# FPGA_DECOUP.net
KiCad netlist of a schematic drawn in Altium Designer
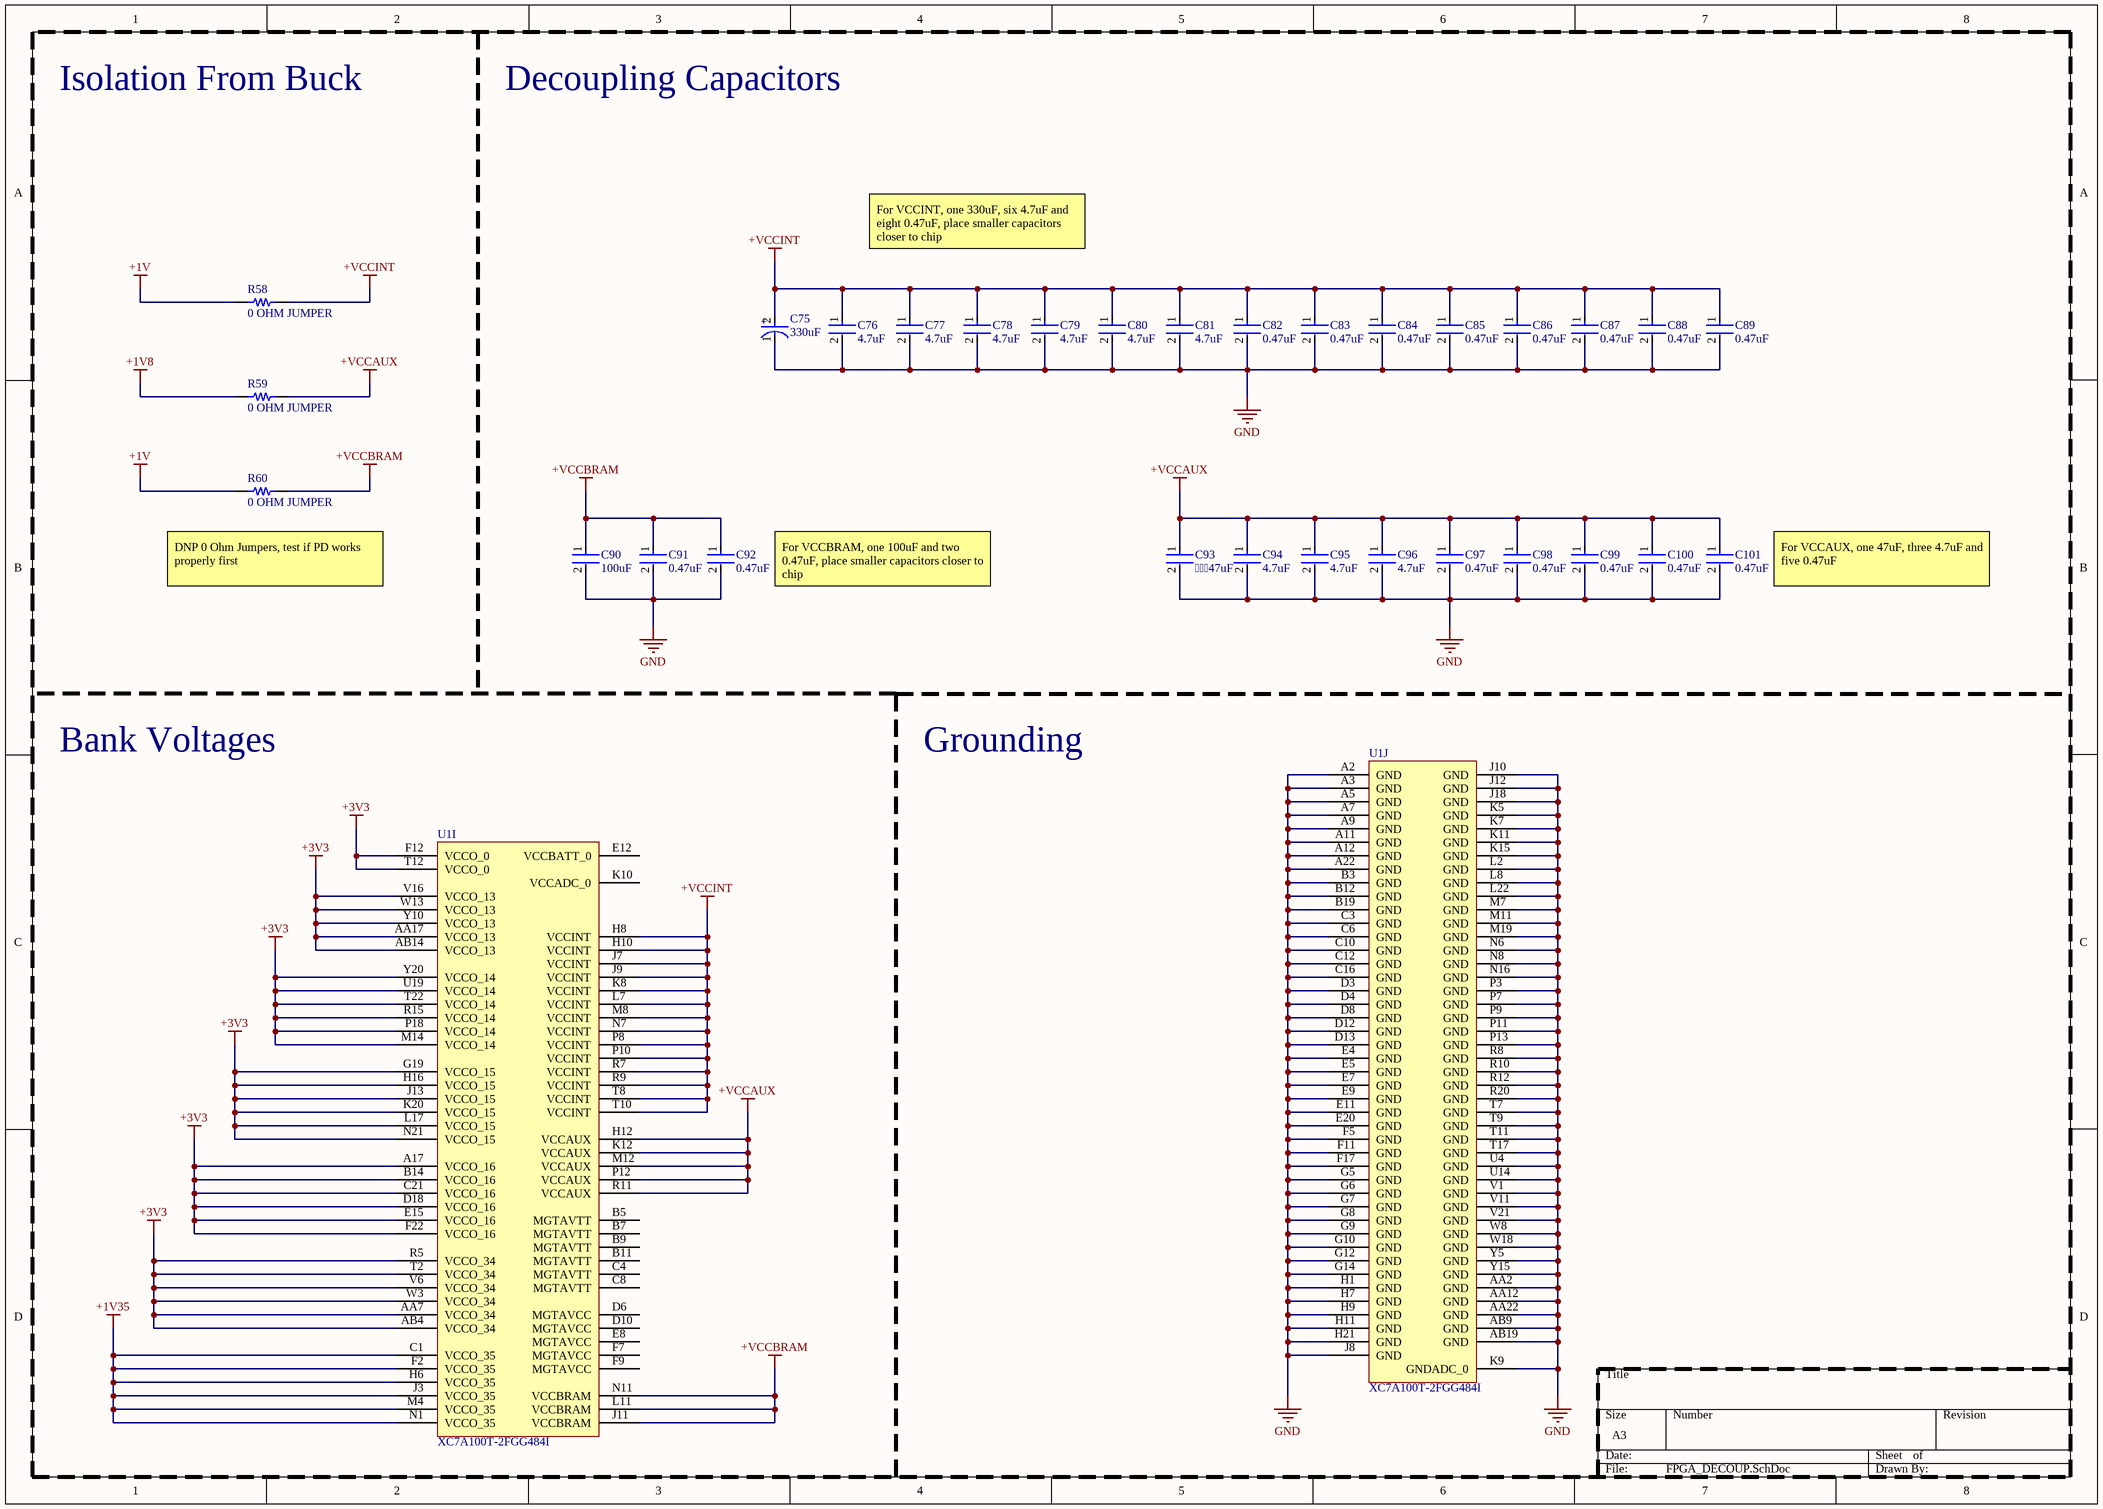
[diagram p0: FPGA_DECOUP.SchDoc]

(export (version "E")
  (design (tool "Eeschema 10.0.6"))
  (components
    (comp (ref "C75")
      (value "330uF")
      (footprint "FP-T495X336M035ATE100-MFG")
      (description "CAP TANT 33UF 20% 35V 2917")
      (fields (field (name "TOLERANCE") "20%"))
      (libsource (lib "Altium Content Vault") (part "203bc49f2ac43e59fd269a8c329ed05"))
    )
    (comp (ref "C76")
      (value "4.7uF")
      (footprint "FP-GRM155-0_1-IPC_B")
      (description "Chip Multilayer Ceramic Capacitors for General Purpose, 0402, 4.7uF, X5R, 15%, 20%, 6.3V")
      (fields (field (name "VOLTAGE") "6.3V") (field (name "TOLERANCE") "20%"))
      (libsource (lib "Altium Content Vault") (part "11868f565c42a9108669ba33697ecf6"))
    )
    (comp (ref "C77")
      (value "4.7uF")
      (footprint "FP-GRM155-0_1-IPC_B")
      (description "Chip Multilayer Ceramic Capacitors for General Purpose, 0402, 4.7uF, X5R, 15%, 20%, 6.3V")
      (fields (field (name "VOLTAGE") "6.3V") (field (name "TOLERANCE") "20%"))
      (libsource (lib "Altium Content Vault") (part "11868f565c42a9108669ba33697ecf6"))
    )
    (comp (ref "C78")
      (value "4.7uF")
      (footprint "FP-GRM155-0_1-IPC_B")
      (description "Chip Multilayer Ceramic Capacitors for General Purpose, 0402, 4.7uF, X5R, 15%, 20%, 6.3V")
      (fields (field (name "VOLTAGE") "6.3V") (field (name "TOLERANCE") "20%"))
      (libsource (lib "Altium Content Vault") (part "11868f565c42a9108669ba33697ecf6"))
    )
    (comp (ref "C79")
      (value "4.7uF")
      (footprint "FP-GRM155-0_1-IPC_B")
      (description "Chip Multilayer Ceramic Capacitors for General Purpose, 0402, 4.7uF, X5R, 15%, 20%, 6.3V")
      (fields (field (name "VOLTAGE") "6.3V") (field (name "TOLERANCE") "20%"))
      (libsource (lib "Altium Content Vault") (part "11868f565c42a9108669ba33697ecf6"))
    )
    (comp (ref "C80")
      (value "4.7uF")
      (footprint "FP-GRM155-0_1-IPC_B")
      (description "Chip Multilayer Ceramic Capacitors for General Purpose, 0402, 4.7uF, X5R, 15%, 20%, 6.3V")
      (fields (field (name "VOLTAGE") "6.3V") (field (name "TOLERANCE") "20%"))
      (libsource (lib "Altium Content Vault") (part "11868f565c42a9108669ba33697ecf6"))
    )
    (comp (ref "C81")
      (value "4.7uF")
      (footprint "FP-GRM155-0_1-IPC_B")
      (description "Chip Multilayer Ceramic Capacitors for General Purpose, 0402, 4.7uF, X5R, 15%, 20%, 6.3V")
      (fields (field (name "VOLTAGE") "6.3V") (field (name "TOLERANCE") "20%"))
      (libsource (lib "Altium Content Vault") (part "11868f565c42a9108669ba33697ecf6"))
    )
    (comp (ref "C82")
      (value "0.47uF")
      (footprint "FP-GRM15-0_1-MFG")
      (description "CAP CER 0.47UF 10V X5R 0402")
      (fields
        (field (name "MANUFACTURER") "Murata Electronics North America")
        (field (name "MANUFACTURER PART NUMBER") "GRM155R61A474KE15D")
      )
      (libsource (lib "Altium Content Vault") (part "11868f565c42a9108669ba33697ecf6"))
    )
    (comp (ref "C83")
      (value "0.47uF")
      (footprint "FP-GRM15-0_1-MFG")
      (description "CAP CER 0.47UF 10V X5R 0402")
      (fields
        (field (name "MANUFACTURER") "Murata Electronics North America")
        (field (name "MANUFACTURER PART NUMBER") "GRM155R61A474KE15D")
      )
      (libsource (lib "Altium Content Vault") (part "11868f565c42a9108669ba33697ecf6"))
    )
    (comp (ref "C84")
      (value "0.47uF")
      (footprint "FP-GRM15-0_1-MFG")
      (description "CAP CER 0.47UF 10V X5R 0402")
      (fields
        (field (name "MANUFACTURER") "Murata Electronics North America")
        (field (name "MANUFACTURER PART NUMBER") "GRM155R61A474KE15D")
      )
      (libsource (lib "Altium Content Vault") (part "11868f565c42a9108669ba33697ecf6"))
    )
    (comp (ref "C85")
      (value "0.47uF")
      (footprint "FP-GRM15-0_1-MFG")
      (description "CAP CER 0.47UF 10V X5R 0402")
      (fields
        (field (name "MANUFACTURER") "Murata Electronics North America")
        (field (name "MANUFACTURER PART NUMBER") "GRM155R61A474KE15D")
      )
      (libsource (lib "Altium Content Vault") (part "11868f565c42a9108669ba33697ecf6"))
    )
    (comp (ref "C86")
      (value "0.47uF")
      (footprint "FP-GRM15-0_1-MFG")
      (description "CAP CER 0.47UF 10V X5R 0402")
      (fields
        (field (name "MANUFACTURER") "Murata Electronics North America")
        (field (name "MANUFACTURER PART NUMBER") "GRM155R61A474KE15D")
      )
      (libsource (lib "Altium Content Vault") (part "11868f565c42a9108669ba33697ecf6"))
    )
    (comp (ref "C87")
      (value "0.47uF")
      (footprint "FP-GRM15-0_1-MFG")
      (description "CAP CER 0.47UF 10V X5R 0402")
      (fields
        (field (name "MANUFACTURER") "Murata Electronics North America")
        (field (name "MANUFACTURER PART NUMBER") "GRM155R61A474KE15D")
      )
      (libsource (lib "Altium Content Vault") (part "11868f565c42a9108669ba33697ecf6"))
    )
    (comp (ref "C88")
      (value "0.47uF")
      (footprint "FP-GRM15-0_1-MFG")
      (description "CAP CER 0.47UF 10V X5R 0402")
      (fields
        (field (name "MANUFACTURER") "Murata Electronics North America")
        (field (name "MANUFACTURER PART NUMBER") "GRM155R61A474KE15D")
      )
      (libsource (lib "Altium Content Vault") (part "11868f565c42a9108669ba33697ecf6"))
    )
    (comp (ref "C89")
      (value "0.47uF")
      (footprint "FP-GRM15-0_1-MFG")
      (description "CAP CER 0.47UF 10V X5R 0402")
      (fields
        (field (name "MANUFACTURER") "Murata Electronics North America")
        (field (name "MANUFACTURER PART NUMBER") "GRM155R61A474KE15D")
      )
      (libsource (lib "Altium Content Vault") (part "11868f565c42a9108669ba33697ecf6"))
    )
    (comp (ref "C90")
      (value "100uF")
      (footprint "FP-GRM32E-0_3-0_2-IPC_B")
      (description "Chip Multilayer Ceramic Capacitors for General Purpose, 1210, 100uF, X5R, 15%, 20%, 10V")
      (fields (field (name "TOLERANCE") "20%") (field (name "VOLTAGE") "10V"))
      (libsource (lib "Altium Content Vault") (part "02cd4be3c70576c341d710602a673aa"))
    )
    (comp (ref "C91")
      (value "0.47uF")
      (footprint "FP-GRM15-0_1-MFG")
      (description "CAP CER 0.47UF 10V X5R 0402")
      (fields
        (field (name "MANUFACTURER") "Murata Electronics North America")
        (field (name "MANUFACTURER PART NUMBER") "GRM155R61A474KE15D")
      )
      (libsource (lib "Altium Content Vault") (part "11868f565c42a9108669ba33697ecf6"))
    )
    (comp (ref "C92")
      (value "0.47uF")
      (footprint "FP-GRM15-0_1-MFG")
      (description "CAP CER 0.47UF 10V X5R 0402")
      (fields
        (field (name "MANUFACTURER") "Murata Electronics North America")
        (field (name "MANUFACTURER PART NUMBER") "GRM155R61A474KE15D")
      )
      (libsource (lib "Altium Content Vault") (part "11868f565c42a9108669ba33697ecf6"))
    )
    (comp (ref "C93")
      (value "47uF")
      (footprint "FP-GRM32E-0_3-0_2-MFG")
      (description "CAP CER 47UF 6.3V X5R 1210")
      (fields (field (name "VOLTAGE") "6.3V") (field (name "TOLERANCE") "10%"))
      (libsource (lib "Altium Content Vault") (part "02cd4be3c70576c341d710602a673aa"))
    )
    (comp (ref "C94")
      (value "4.7uF")
      (footprint "FP-GRM155-0_1-IPC_B")
      (description "Chip Multilayer Ceramic Capacitors for General Purpose, 0402, 4.7uF, X5R, 15%, 20%, 6.3V")
      (fields (field (name "VOLTAGE") "6.3V") (field (name "TOLERANCE") "20%"))
      (libsource (lib "Altium Content Vault") (part "11868f565c42a9108669ba33697ecf6"))
    )
    (comp (ref "C95")
      (value "4.7uF")
      (footprint "FP-GRM155-0_1-IPC_B")
      (description "Chip Multilayer Ceramic Capacitors for General Purpose, 0402, 4.7uF, X5R, 15%, 20%, 6.3V")
      (fields (field (name "VOLTAGE") "6.3V") (field (name "TOLERANCE") "20%"))
      (libsource (lib "Altium Content Vault") (part "11868f565c42a9108669ba33697ecf6"))
    )
    (comp (ref "C96")
      (value "4.7uF")
      (footprint "FP-GRM155-0_1-IPC_B")
      (description "Chip Multilayer Ceramic Capacitors for General Purpose, 0402, 4.7uF, X5R, 15%, 20%, 6.3V")
      (fields (field (name "VOLTAGE") "6.3V") (field (name "TOLERANCE") "20%"))
      (libsource (lib "Altium Content Vault") (part "11868f565c42a9108669ba33697ecf6"))
    )
    (comp (ref "C97")
      (value "0.47uF")
      (footprint "FP-GRM15-0_1-MFG")
      (description "CAP CER 0.47UF 10V X5R 0402")
      (fields
        (field (name "MANUFACTURER") "Murata Electronics North America")
        (field (name "MANUFACTURER PART NUMBER") "GRM155R61A474KE15D")
      )
      (libsource (lib "Altium Content Vault") (part "11868f565c42a9108669ba33697ecf6"))
    )
    (comp (ref "C98")
      (value "0.47uF")
      (footprint "FP-GRM15-0_1-MFG")
      (description "CAP CER 0.47UF 10V X5R 0402")
      (fields
        (field (name "MANUFACTURER") "Murata Electronics North America")
        (field (name "MANUFACTURER PART NUMBER") "GRM155R61A474KE15D")
      )
      (libsource (lib "Altium Content Vault") (part "11868f565c42a9108669ba33697ecf6"))
    )
    (comp (ref "C99")
      (value "0.47uF")
      (footprint "FP-GRM15-0_1-MFG")
      (description "CAP CER 0.47UF 10V X5R 0402")
      (fields
        (field (name "MANUFACTURER") "Murata Electronics North America")
        (field (name "MANUFACTURER PART NUMBER") "GRM155R61A474KE15D")
      )
      (libsource (lib "Altium Content Vault") (part "11868f565c42a9108669ba33697ecf6"))
    )
    (comp (ref "C100")
      (value "0.47uF")
      (footprint "FP-GRM15-0_1-MFG")
      (description "CAP CER 0.47UF 10V X5R 0402")
      (fields
        (field (name "MANUFACTURER") "Murata Electronics North America")
        (field (name "MANUFACTURER PART NUMBER") "GRM155R61A474KE15D")
      )
      (libsource (lib "Altium Content Vault") (part "11868f565c42a9108669ba33697ecf6"))
    )
    (comp (ref "C101")
      (value "0.47uF")
      (footprint "FP-GRM15-0_1-MFG")
      (description "CAP CER 0.47UF 10V X5R 0402")
      (fields
        (field (name "MANUFACTURER") "Murata Electronics North America")
        (field (name "MANUFACTURER PART NUMBER") "GRM155R61A474KE15D")
      )
      (libsource (lib "Altium Content Vault") (part "11868f565c42a9108669ba33697ecf6"))
    )
    (comp (ref "R58")
      (value "0 OHM JUMPER")
      (footprint "RES 0603_1608")
      (description "Fixed Resistor, Metal Glaze/thick Film, 0.1W, 0ohm, Surface Mount, 0603")
      (libsource (lib "Midnight Sun") (part "Resistor"))
    )
    (comp (ref "R59")
      (value "0 OHM JUMPER")
      (footprint "RES 0603_1608")
      (description "Fixed Resistor, Metal Glaze/thick Film, 0.1W, 0ohm, Surface Mount, 0603")
      (libsource (lib "Midnight Sun") (part "Resistor"))
    )
    (comp (ref "R60")
      (value "0 OHM JUMPER")
      (footprint "RES 0603_1608")
      (description "Fixed Resistor, Metal Glaze/thick Film, 0.1W, 0ohm, Surface Mount, 0603")
      (libsource (lib "Midnight Sun") (part "Resistor"))
    )
    (comp (ref "U1")
      (value "XC7A100T-2FGG484I")
      (footprint "FGG484")
      (description "Artix-7 FPGA, 285 User I/Os, 4 GTP, 484-Ball BGA, Speed Grade 2, Industrial Grade, Pb-Free")
      (fields (field (name "MANUFACTURER") "Xilinx") (field (name "GENERIC PART NUMBER") "XC7A100T"))
      (libsource (lib "Altium Content Vault") (part "XNLX-XC7A100T-XNLX-FGG484"))
    )
  )
  (nets
    (net (code "1") (name "+1V") (class "Default")
      (node (ref "R58") (pin "1") (pinfunction "1_1") (pintype "passive"))
      (node (ref "R60") (pin "1") (pinfunction "1_1") (pintype "passive"))
    )
    (net (code "2") (name "+1V8") (class "Default")
      (node (ref "R59") (pin "1") (pinfunction "1_1") (pintype "passive"))
    )
    (net (code "3") (name "+1V35") (class "Default")
      (node (ref "U1") (pin "C1") (pinfunction "VCCO_35_C1") (pintype "power_in"))
      (node (ref "U1") (pin "F2") (pinfunction "VCCO_35_F2") (pintype "power_in"))
      (node (ref "U1") (pin "H6") (pinfunction "VCCO_35_H6") (pintype "power_in"))
      (node (ref "U1") (pin "J3") (pinfunction "VCCO_35_J3") (pintype "power_in"))
      (node (ref "U1") (pin "M4") (pinfunction "VCCO_35_M4") (pintype "power_in"))
      (node (ref "U1") (pin "N1") (pinfunction "VCCO_35_N1") (pintype "power_in"))
    )
    (net (code "4") (name "+3V3") (class "Default")
      (node (ref "U1") (pin "A17") (pinfunction "VCCO_16_A17") (pintype "power_in"))
      (node (ref "U1") (pin "AA17") (pinfunction "VCCO_13_AA17") (pintype "power_in"))
      (node (ref "U1") (pin "AA7") (pinfunction "VCCO_34_AA7") (pintype "power_in"))
      (node (ref "U1") (pin "AB14") (pinfunction "VCCO_13_AB14") (pintype "power_in"))
      (node (ref "U1") (pin "AB4") (pinfunction "VCCO_34_AB4") (pintype "power_in"))
      (node (ref "U1") (pin "B14") (pinfunction "VCCO_16_B14") (pintype "power_in"))
      (node (ref "U1") (pin "C21") (pinfunction "VCCO_16_C21") (pintype "power_in"))
      (node (ref "U1") (pin "D18") (pinfunction "VCCO_16_D18") (pintype "power_in"))
      (node (ref "U1") (pin "E15") (pinfunction "VCCO_16_E15") (pintype "power_in"))
      (node (ref "U1") (pin "F12") (pinfunction "VCCO_0_F12") (pintype "power_in"))
      (node (ref "U1") (pin "F22") (pinfunction "VCCO_16_F22") (pintype "power_in"))
      (node (ref "U1") (pin "G19") (pinfunction "VCCO_15_G19") (pintype "power_in"))
      (node (ref "U1") (pin "H16") (pinfunction "VCCO_15_H16") (pintype "power_in"))
      (node (ref "U1") (pin "J13") (pinfunction "VCCO_15_J13") (pintype "power_in"))
      (node (ref "U1") (pin "K20") (pinfunction "VCCO_15_K20") (pintype "power_in"))
      (node (ref "U1") (pin "L17") (pinfunction "VCCO_15_L17") (pintype "power_in"))
      (node (ref "U1") (pin "M14") (pinfunction "VCCO_14_M14") (pintype "power_in"))
      (node (ref "U1") (pin "N21") (pinfunction "VCCO_15_N21") (pintype "power_in"))
      (node (ref "U1") (pin "P18") (pinfunction "VCCO_14_P18") (pintype "power_in"))
      (node (ref "U1") (pin "R15") (pinfunction "VCCO_14_R15") (pintype "power_in"))
      (node (ref "U1") (pin "R5") (pinfunction "VCCO_34_R5") (pintype "power_in"))
      (node (ref "U1") (pin "T12") (pinfunction "VCCO_0_T12") (pintype "power_in"))
      (node (ref "U1") (pin "T2") (pinfunction "VCCO_34_T2") (pintype "power_in"))
      (node (ref "U1") (pin "T22") (pinfunction "VCCO_14_T22") (pintype "power_in"))
      (node (ref "U1") (pin "U19") (pinfunction "VCCO_14_U19") (pintype "power_in"))
      (node (ref "U1") (pin "V16") (pinfunction "VCCO_13_V16") (pintype "power_in"))
      (node (ref "U1") (pin "V6") (pinfunction "VCCO_34_V6") (pintype "power_in"))
      (node (ref "U1") (pin "W13") (pinfunction "VCCO_13_W13") (pintype "power_in"))
      (node (ref "U1") (pin "W3") (pinfunction "VCCO_34_W3") (pintype "power_in"))
      (node (ref "U1") (pin "Y10") (pinfunction "VCCO_13_Y10") (pintype "power_in"))
      (node (ref "U1") (pin "Y20") (pinfunction "VCCO_14_Y20") (pintype "power_in"))
    )
    (net (code "5") (name "+VCCAUX") (class "Default")
      (node (ref "C100") (pin "1") (pinfunction "1_1") (pintype "passive"))
      (node (ref "C101") (pin "1") (pinfunction "1_1") (pintype "passive"))
      (node (ref "C93") (pin "1") (pinfunction "1_1") (pintype "passive"))
      (node (ref "C94") (pin "1") (pinfunction "1_1") (pintype "passive"))
      (node (ref "C95") (pin "1") (pinfunction "1_1") (pintype "passive"))
      (node (ref "C96") (pin "1") (pinfunction "1_1") (pintype "passive"))
      (node (ref "C97") (pin "1") (pinfunction "1_1") (pintype "passive"))
      (node (ref "C98") (pin "1") (pinfunction "1_1") (pintype "passive"))
      (node (ref "C99") (pin "1") (pinfunction "1_1") (pintype "passive"))
      (node (ref "R59") (pin "2") (pinfunction "2_2") (pintype "passive"))
      (node (ref "U1") (pin "H12") (pinfunction "VCCAUX_H12") (pintype "power_in"))
      (node (ref "U1") (pin "K12") (pinfunction "VCCAUX_K12") (pintype "power_in"))
      (node (ref "U1") (pin "M12") (pinfunction "VCCAUX_M12") (pintype "power_in"))
      (node (ref "U1") (pin "P12") (pinfunction "VCCAUX_P12") (pintype "power_in"))
      (node (ref "U1") (pin "R11") (pinfunction "VCCAUX_R11") (pintype "power_in"))
    )
    (net (code "6") (name "+VCCBRAM") (class "Default")
      (node (ref "C90") (pin "1") (pinfunction "1_1") (pintype "passive"))
      (node (ref "C91") (pin "1") (pinfunction "1_1") (pintype "passive"))
      (node (ref "C92") (pin "1") (pinfunction "1_1") (pintype "passive"))
      (node (ref "R60") (pin "2") (pinfunction "2_2") (pintype "passive"))
      (node (ref "U1") (pin "J11") (pinfunction "VCCBRAM_J11") (pintype "power_in"))
      (node (ref "U1") (pin "L11") (pinfunction "VCCBRAM_L11") (pintype "power_in"))
      (node (ref "U1") (pin "N11") (pinfunction "VCCBRAM_N11") (pintype "power_in"))
    )
    (net (code "7") (name "+VCCINT") (class "Default")
      (node (ref "C75") (pin "2") (pinfunction "A_2") (pintype "passive"))
      (node (ref "C76") (pin "1") (pinfunction "1_1") (pintype "passive"))
      (node (ref "C77") (pin "1") (pinfunction "1_1") (pintype "passive"))
      (node (ref "C78") (pin "1") (pinfunction "1_1") (pintype "passive"))
      (node (ref "C79") (pin "1") (pinfunction "1_1") (pintype "passive"))
      (node (ref "C80") (pin "1") (pinfunction "1_1") (pintype "passive"))
      (node (ref "C81") (pin "1") (pinfunction "1_1") (pintype "passive"))
      (node (ref "C82") (pin "1") (pinfunction "1_1") (pintype "passive"))
      (node (ref "C83") (pin "1") (pinfunction "1_1") (pintype "passive"))
      (node (ref "C84") (pin "1") (pinfunction "1_1") (pintype "passive"))
      (node (ref "C85") (pin "1") (pinfunction "1_1") (pintype "passive"))
      (node (ref "C86") (pin "1") (pinfunction "1_1") (pintype "passive"))
      (node (ref "C87") (pin "1") (pinfunction "1_1") (pintype "passive"))
      (node (ref "C88") (pin "1") (pinfunction "1_1") (pintype "passive"))
      (node (ref "C89") (pin "1") (pinfunction "1_1") (pintype "passive"))
      (node (ref "R58") (pin "2") (pinfunction "2_2") (pintype "passive"))
      (node (ref "U1") (pin "H10") (pinfunction "VCCINT_H10") (pintype "power_in"))
      (node (ref "U1") (pin "H8") (pinfunction "VCCINT_H8") (pintype "power_in"))
      (node (ref "U1") (pin "J7") (pinfunction "VCCINT_J7") (pintype "power_in"))
      (node (ref "U1") (pin "J9") (pinfunction "VCCINT_J9") (pintype "power_in"))
      (node (ref "U1") (pin "K8") (pinfunction "VCCINT_K8") (pintype "power_in"))
      (node (ref "U1") (pin "L7") (pinfunction "VCCINT_L7") (pintype "power_in"))
      (node (ref "U1") (pin "M8") (pinfunction "VCCINT_M8") (pintype "power_in"))
      (node (ref "U1") (pin "N7") (pinfunction "VCCINT_N7") (pintype "power_in"))
      (node (ref "U1") (pin "P10") (pinfunction "VCCINT_P10") (pintype "power_in"))
      (node (ref "U1") (pin "P8") (pinfunction "VCCINT_P8") (pintype "power_in"))
      (node (ref "U1") (pin "R7") (pinfunction "VCCINT_R7") (pintype "power_in"))
      (node (ref "U1") (pin "R9") (pinfunction "VCCINT_R9") (pintype "power_in"))
      (node (ref "U1") (pin "T10") (pinfunction "VCCINT_T10") (pintype "power_in"))
      (node (ref "U1") (pin "T8") (pinfunction "VCCINT_T8") (pintype "power_in"))
    )
    (net (code "8") (name "GND") (class "Default")
      (node (ref "C100") (pin "2") (pinfunction "2_2") (pintype "passive"))
      (node (ref "C101") (pin "2") (pinfunction "2_2") (pintype "passive"))
      (node (ref "C75") (pin "1") (pinfunction "C_1") (pintype "passive"))
      (node (ref "C76") (pin "2") (pinfunction "2_2") (pintype "passive"))
      (node (ref "C77") (pin "2") (pinfunction "2_2") (pintype "passive"))
      (node (ref "C78") (pin "2") (pinfunction "2_2") (pintype "passive"))
      (node (ref "C79") (pin "2") (pinfunction "2_2") (pintype "passive"))
      (node (ref "C80") (pin "2") (pinfunction "2_2") (pintype "passive"))
      (node (ref "C81") (pin "2") (pinfunction "2_2") (pintype "passive"))
      (node (ref "C82") (pin "2") (pinfunction "2_2") (pintype "passive"))
      (node (ref "C83") (pin "2") (pinfunction "2_2") (pintype "passive"))
      (node (ref "C84") (pin "2") (pinfunction "2_2") (pintype "passive"))
      (node (ref "C85") (pin "2") (pinfunction "2_2") (pintype "passive"))
      (node (ref "C86") (pin "2") (pinfunction "2_2") (pintype "passive"))
      (node (ref "C87") (pin "2") (pinfunction "2_2") (pintype "passive"))
      (node (ref "C88") (pin "2") (pinfunction "2_2") (pintype "passive"))
      (node (ref "C89") (pin "2") (pinfunction "2_2") (pintype "passive"))
      (node (ref "C90") (pin "2") (pinfunction "2_2") (pintype "passive"))
      (node (ref "C91") (pin "2") (pinfunction "2_2") (pintype "passive"))
      (node (ref "C92") (pin "2") (pinfunction "2_2") (pintype "passive"))
      (node (ref "C93") (pin "2") (pinfunction "2_2") (pintype "passive"))
      (node (ref "C94") (pin "2") (pinfunction "2_2") (pintype "passive"))
      (node (ref "C95") (pin "2") (pinfunction "2_2") (pintype "passive"))
      (node (ref "C96") (pin "2") (pinfunction "2_2") (pintype "passive"))
      (node (ref "C97") (pin "2") (pinfunction "2_2") (pintype "passive"))
      (node (ref "C98") (pin "2") (pinfunction "2_2") (pintype "passive"))
      (node (ref "C99") (pin "2") (pinfunction "2_2") (pintype "passive"))
      (node (ref "U1") (pin "A11") (pinfunction "GND_A11") (pintype "power_in"))
      (node (ref "U1") (pin "A12") (pinfunction "GND_A12") (pintype "power_in"))
      (node (ref "U1") (pin "A2") (pinfunction "GND_A2") (pintype "power_in"))
      (node (ref "U1") (pin "A22") (pinfunction "GND_A22") (pintype "power_in"))
      (node (ref "U1") (pin "A3") (pinfunction "GND_A3") (pintype "power_in"))
      (node (ref "U1") (pin "A5") (pinfunction "GND_A5") (pintype "power_in"))
      (node (ref "U1") (pin "A7") (pinfunction "GND_A7") (pintype "power_in"))
      (node (ref "U1") (pin "A9") (pinfunction "GND_A9") (pintype "power_in"))
      (node (ref "U1") (pin "AA12") (pinfunction "GND_AA12") (pintype "power_in"))
      (node (ref "U1") (pin "AA2") (pinfunction "GND_AA2") (pintype "power_in"))
      (node (ref "U1") (pin "AA22") (pinfunction "GND_AA22") (pintype "power_in"))
      (node (ref "U1") (pin "AB19") (pinfunction "GND_AB19") (pintype "power_in"))
      (node (ref "U1") (pin "AB9") (pinfunction "GND_AB9") (pintype "power_in"))
      (node (ref "U1") (pin "B12") (pinfunction "GND_B12") (pintype "power_in"))
      (node (ref "U1") (pin "B19") (pinfunction "GND_B19") (pintype "power_in"))
      (node (ref "U1") (pin "B3") (pinfunction "GND_B3") (pintype "power_in"))
      (node (ref "U1") (pin "C10") (pinfunction "GND_C10") (pintype "power_in"))
      (node (ref "U1") (pin "C12") (pinfunction "GND_C12") (pintype "power_in"))
      (node (ref "U1") (pin "C16") (pinfunction "GND_C16") (pintype "power_in"))
      (node (ref "U1") (pin "C3") (pinfunction "GND_C3") (pintype "power_in"))
      (node (ref "U1") (pin "C6") (pinfunction "GND_C6") (pintype "power_in"))
      (node (ref "U1") (pin "D12") (pinfunction "GND_D12") (pintype "power_in"))
      (node (ref "U1") (pin "D13") (pinfunction "GND_D13") (pintype "power_in"))
      (node (ref "U1") (pin "D3") (pinfunction "GND_D3") (pintype "power_in"))
      (node (ref "U1") (pin "D4") (pinfunction "GND_D4") (pintype "power_in"))
      (node (ref "U1") (pin "D8") (pinfunction "GND_D8") (pintype "power_in"))
      (node (ref "U1") (pin "E11") (pinfunction "GND_E11") (pintype "power_in"))
      (node (ref "U1") (pin "E20") (pinfunction "GND_E20") (pintype "power_in"))
      (node (ref "U1") (pin "E4") (pinfunction "GND_E4") (pintype "power_in"))
      (node (ref "U1") (pin "E5") (pinfunction "GND_E5") (pintype "power_in"))
      (node (ref "U1") (pin "E7") (pinfunction "GND_E7") (pintype "power_in"))
      (node (ref "U1") (pin "E9") (pinfunction "GND_E9") (pintype "power_in"))
      (node (ref "U1") (pin "F11") (pinfunction "GND_F11") (pintype "power_in"))
      (node (ref "U1") (pin "F17") (pinfunction "GND_F17") (pintype "power_in"))
      (node (ref "U1") (pin "F5") (pinfunction "GND_F5") (pintype "power_in"))
      (node (ref "U1") (pin "G10") (pinfunction "GND_G10") (pintype "power_in"))
      (node (ref "U1") (pin "G12") (pinfunction "GND_G12") (pintype "power_in"))
      (node (ref "U1") (pin "G14") (pinfunction "GND_G14") (pintype "power_in"))
      (node (ref "U1") (pin "G5") (pinfunction "GND_G5") (pintype "power_in"))
      (node (ref "U1") (pin "G6") (pinfunction "GND_G6") (pintype "power_in"))
      (node (ref "U1") (pin "G7") (pinfunction "GND_G7") (pintype "power_in"))
      (node (ref "U1") (pin "G8") (pinfunction "GND_G8") (pintype "power_in"))
      (node (ref "U1") (pin "G9") (pinfunction "GND_G9") (pintype "power_in"))
      (node (ref "U1") (pin "H1") (pinfunction "GND_H1") (pintype "power_in"))
      (node (ref "U1") (pin "H11") (pinfunction "GND_H11") (pintype "power_in"))
      (node (ref "U1") (pin "H21") (pinfunction "GND_H21") (pintype "power_in"))
      (node (ref "U1") (pin "H7") (pinfunction "GND_H7") (pintype "power_in"))
      (node (ref "U1") (pin "H9") (pinfunction "GND_H9") (pintype "power_in"))
      (node (ref "U1") (pin "J10") (pinfunction "GND_J10") (pintype "power_in"))
      (node (ref "U1") (pin "J12") (pinfunction "GND_J12") (pintype "power_in"))
      (node (ref "U1") (pin "J18") (pinfunction "GND_J18") (pintype "power_in"))
      (node (ref "U1") (pin "J8") (pinfunction "GND_J8") (pintype "power_in"))
      (node (ref "U1") (pin "K11") (pinfunction "GND_K11") (pintype "power_in"))
      (node (ref "U1") (pin "K15") (pinfunction "GND_K15") (pintype "power_in"))
      (node (ref "U1") (pin "K5") (pinfunction "GND_K5") (pintype "power_in"))
      (node (ref "U1") (pin "K7") (pinfunction "GND_K7") (pintype "power_in"))
      (node (ref "U1") (pin "K9") (pinfunction "GNDADC_0_K9") (pintype "power_in"))
      (node (ref "U1") (pin "L2") (pinfunction "GND_L2") (pintype "power_in"))
      (node (ref "U1") (pin "L22") (pinfunction "GND_L22") (pintype "power_in"))
      (node (ref "U1") (pin "L8") (pinfunction "GND_L8") (pintype "power_in"))
      (node (ref "U1") (pin "M11") (pinfunction "GND_M11") (pintype "power_in"))
      (node (ref "U1") (pin "M19") (pinfunction "GND_M19") (pintype "power_in"))
      (node (ref "U1") (pin "M7") (pinfunction "GND_M7") (pintype "power_in"))
      (node (ref "U1") (pin "N16") (pinfunction "GND_N16") (pintype "power_in"))
      (node (ref "U1") (pin "N6") (pinfunction "GND_N6") (pintype "power_in"))
      (node (ref "U1") (pin "N8") (pinfunction "GND_N8") (pintype "power_in"))
      (node (ref "U1") (pin "P11") (pinfunction "GND_P11") (pintype "power_in"))
      (node (ref "U1") (pin "P13") (pinfunction "GND_P13") (pintype "power_in"))
      (node (ref "U1") (pin "P3") (pinfunction "GND_P3") (pintype "power_in"))
      (node (ref "U1") (pin "P7") (pinfunction "GND_P7") (pintype "power_in"))
      (node (ref "U1") (pin "P9") (pinfunction "GND_P9") (pintype "power_in"))
      (node (ref "U1") (pin "R10") (pinfunction "GND_R10") (pintype "power_in"))
      (node (ref "U1") (pin "R12") (pinfunction "GND_R12") (pintype "power_in"))
      (node (ref "U1") (pin "R20") (pinfunction "GND_R20") (pintype "power_in"))
      (node (ref "U1") (pin "R8") (pinfunction "GND_R8") (pintype "power_in"))
      (node (ref "U1") (pin "T11") (pinfunction "GND_T11") (pintype "power_in"))
      (node (ref "U1") (pin "T17") (pinfunction "GND_T17") (pintype "power_in"))
      (node (ref "U1") (pin "T7") (pinfunction "GND_T7") (pintype "power_in"))
      (node (ref "U1") (pin "T9") (pinfunction "GND_T9") (pintype "power_in"))
      (node (ref "U1") (pin "U14") (pinfunction "GND_U14") (pintype "power_in"))
      (node (ref "U1") (pin "U4") (pinfunction "GND_U4") (pintype "power_in"))
      (node (ref "U1") (pin "V1") (pinfunction "GND_V1") (pintype "power_in"))
      (node (ref "U1") (pin "V11") (pinfunction "GND_V11") (pintype "power_in"))
      (node (ref "U1") (pin "V21") (pinfunction "GND_V21") (pintype "power_in"))
      (node (ref "U1") (pin "W18") (pinfunction "GND_W18") (pintype "power_in"))
      (node (ref "U1") (pin "W8") (pinfunction "GND_W8") (pintype "power_in"))
      (node (ref "U1") (pin "Y15") (pinfunction "GND_Y15") (pintype "power_in"))
      (node (ref "U1") (pin "Y5") (pinfunction "GND_Y5") (pintype "power_in"))
    )
    (net (code "9") (name "unconnected-(U1I-MGTAVCC-PadD6)") (class "Default")
      (node (ref "U1") (pin "D6") (pinfunction "MGTAVCC_D6") (pintype "power_in"))
    )
    (net (code "10") (name "unconnected-(U1I-MGTAVCC-PadD10)") (class "Default")
      (node (ref "U1") (pin "D10") (pinfunction "MGTAVCC_D10") (pintype "power_in"))
    )
    (net (code "11") (name "unconnected-(U1I-MGTAVCC-PadE8)") (class "Default")
      (node (ref "U1") (pin "E8") (pinfunction "MGTAVCC_E8") (pintype "power_in"))
    )
    (net (code "12") (name "unconnected-(U1I-MGTAVCC-PadF7)") (class "Default")
      (node (ref "U1") (pin "F7") (pinfunction "MGTAVCC_F7") (pintype "power_in"))
    )
    (net (code "13") (name "unconnected-(U1I-MGTAVCC-PadF9)") (class "Default")
      (node (ref "U1") (pin "F9") (pinfunction "MGTAVCC_F9") (pintype "power_in"))
    )
    (net (code "14") (name "unconnected-(U1I-MGTAVTT-PadB5)") (class "Default")
      (node (ref "U1") (pin "B5") (pinfunction "MGTAVTT_B5") (pintype "power_in"))
    )
    (net (code "15") (name "unconnected-(U1I-MGTAVTT-PadB7)") (class "Default")
      (node (ref "U1") (pin "B7") (pinfunction "MGTAVTT_B7") (pintype "power_in"))
    )
    (net (code "16") (name "unconnected-(U1I-MGTAVTT-PadB9)") (class "Default")
      (node (ref "U1") (pin "B9") (pinfunction "MGTAVTT_B9") (pintype "power_in"))
    )
    (net (code "17") (name "unconnected-(U1I-MGTAVTT-PadB11)") (class "Default")
      (node (ref "U1") (pin "B11") (pinfunction "MGTAVTT_B11") (pintype "power_in"))
    )
    (net (code "18") (name "unconnected-(U1I-MGTAVTT-PadC4)") (class "Default")
      (node (ref "U1") (pin "C4") (pinfunction "MGTAVTT_C4") (pintype "power_in"))
    )
    (net (code "19") (name "unconnected-(U1I-MGTAVTT-PadC8)") (class "Default")
      (node (ref "U1") (pin "C8") (pinfunction "MGTAVTT_C8") (pintype "power_in"))
    )
    (net (code "20") (name "unconnected-(U1I-VCCADC_0-PadK10)") (class "Default")
      (node (ref "U1") (pin "K10") (pinfunction "VCCADC_0_K10") (pintype "power_in"))
    )
    (net (code "21") (name "unconnected-(U1I-VCCBATT_0-PadE12)") (class "Default")
      (node (ref "U1") (pin "E12") (pinfunction "VCCBATT_0_E12") (pintype "power_in"))
    )
  )
)
